# Sheet3.net
KiCad netlist of a schematic drawn in Altium Designer
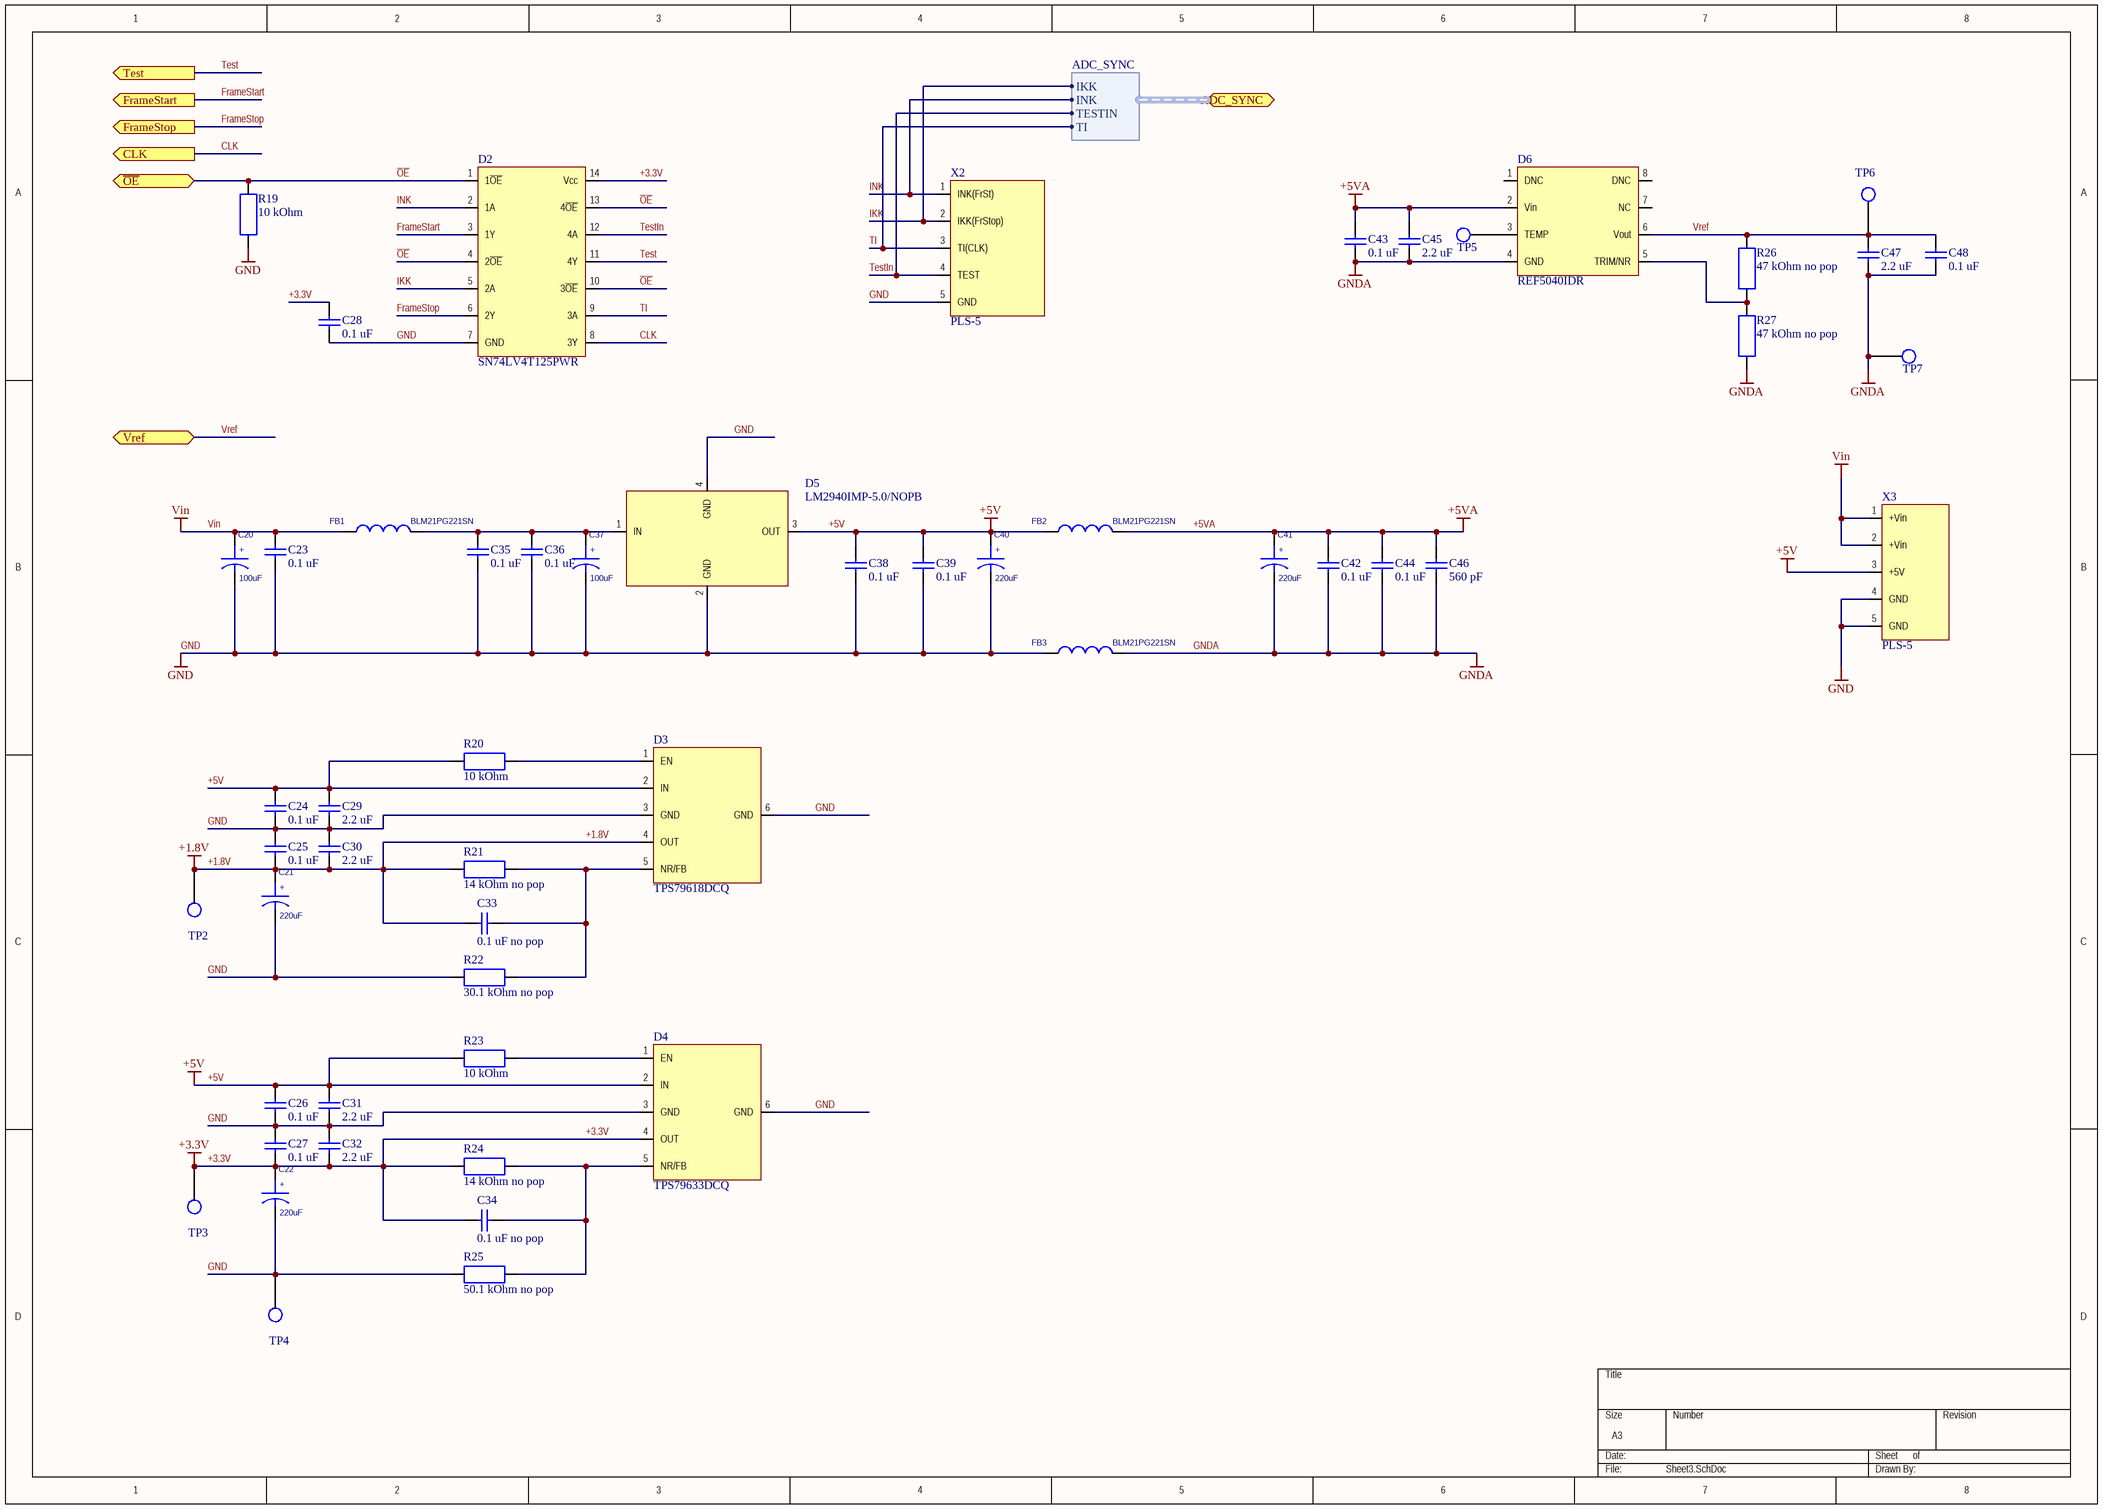
[diagram p0: Sheet3.SchDoc]

(export (version "E")
  (design (tool "Eeschema 10.0.6"))
  (components
    (comp (ref "C20")
      (value "100uF")
      (footprint "TC7343-2917")
      (fields
        (field (name "VENDOR PART#") "495-2256-1-ND")
        (field (name "MFG PART#") "B45196H3107M409")
        (field (name "MFG") "Kemet")
      )
      (libsource (lib "ADClib") (part "CAP TANTAL CASE E"))
    )
    (comp (ref "C21")
      (value "220uF")
      (footprint "TC7343-2917")
      (fields
        (field (name "VENDOR PART#") "495-2256-1-ND")
        (field (name "MFG PART#") "B45196H3107M409")
        (field (name "MFG") "Kemet")
      )
      (libsource (lib "ADClib") (part "CAP TANTAL CASE E"))
    )
    (comp (ref "C22")
      (value "220uF")
      (footprint "TC7343-2917")
      (fields
        (field (name "VENDOR PART#") "495-2256-1-ND")
        (field (name "MFG PART#") "B45196H3107M409")
        (field (name "MFG") "Kemet")
      )
      (libsource (lib "ADClib") (part "CAP TANTAL CASE E"))
    )
    (comp (ref "C23")
      (value "0.1 uF")
      (footprint "CAPC1608N")
      (description "±10%, X7R, 0603")
      (fields (field (name "PUBLISHER") "DS"))
      (libsource (lib "ADClib") (part "CC0603"))
    )
    (comp (ref "C24")
      (value "0.1 uF")
      (footprint "CAPC1608N")
      (description "±10%, X7R, 0603")
      (fields (field (name "PUBLISHER") "DS"))
      (libsource (lib "ADClib") (part "CC0603"))
    )
    (comp (ref "C25")
      (value "0.1 uF")
      (footprint "CAPC1608N")
      (description "±10%, X7R, 0603")
      (fields (field (name "PUBLISHER") "DS"))
      (libsource (lib "ADClib") (part "CC0603"))
    )
    (comp (ref "C26")
      (value "0.1 uF")
      (footprint "CAPC1608N")
      (description "±10%, X7R, 0603")
      (fields (field (name "PUBLISHER") "DS"))
      (libsource (lib "ADClib") (part "CC0603"))
    )
    (comp (ref "C27")
      (value "0.1 uF")
      (footprint "CAPC1608N")
      (description "±10%, X7R, 0603")
      (fields (field (name "PUBLISHER") "DS"))
      (libsource (lib "ADClib") (part "CC0603"))
    )
    (comp (ref "C28")
      (value "0.1 uF")
      (footprint "CAPC1608N")
      (description "±10%, X7R, 0603")
      (fields (field (name "PUBLISHER") "DS"))
      (libsource (lib "ADClib") (part "CC0603"))
    )
    (comp (ref "C29")
      (value "2.2 uF")
      (footprint "CAPC1608N")
      (description "±10%, X7R, 0603")
      (fields (field (name "PUBLISHER") "DS"))
      (libsource (lib "ADClib") (part "CC0603"))
    )
    (comp (ref "C30")
      (value "2.2 uF")
      (footprint "CAPC1608N")
      (description "±10%, X7R, 0603")
      (fields (field (name "PUBLISHER") "DS"))
      (libsource (lib "ADClib") (part "CC0603"))
    )
    (comp (ref "C31")
      (value "2.2 uF")
      (footprint "CAPC1608N")
      (description "±10%, X7R, 0603")
      (fields (field (name "PUBLISHER") "DS"))
      (libsource (lib "ADClib") (part "CC0603"))
    )
    (comp (ref "C32")
      (value "2.2 uF")
      (footprint "CAPC1608N")
      (description "±10%, X7R, 0603")
      (fields (field (name "PUBLISHER") "DS"))
      (libsource (lib "ADClib") (part "CC0603"))
    )
    (comp (ref "C33")
      (value "0.1 uF no pop")
      (footprint "CAPC1608N")
      (description "±10%, X7R, 0603")
      (fields (field (name "PUBLISHER") "DS"))
      (libsource (lib "ADClib") (part "CC0603"))
    )
    (comp (ref "C34")
      (value "0.1 uF no pop")
      (footprint "CAPC1608N")
      (description "±10%, X7R, 0603")
      (fields (field (name "PUBLISHER") "DS"))
      (libsource (lib "ADClib") (part "CC0603"))
    )
    (comp (ref "C35")
      (value "0.1 uF")
      (footprint "CAPC1608N")
      (description "±10%, X7R, 0603")
      (fields (field (name "PUBLISHER") "DS"))
      (libsource (lib "ADClib") (part "CC0603"))
    )
    (comp (ref "C36")
      (value "0.1 uF")
      (footprint "CAPC1608N")
      (description "±10%, X7R, 0603")
      (fields (field (name "PUBLISHER") "DS"))
      (libsource (lib "ADClib") (part "CC0603"))
    )
    (comp (ref "C37")
      (value "100uF")
      (footprint "TC7343-2917")
      (fields
        (field (name "VENDOR PART#") "495-2256-1-ND")
        (field (name "MFG PART#") "B45196H3107M409")
        (field (name "MFG") "Kemet")
      )
      (libsource (lib "ADClib") (part "CAP TANTAL CASE E"))
    )
    (comp (ref "C38")
      (value "0.1 uF")
      (footprint "CAPC1608N")
      (description "±10%, X7R, 0603")
      (fields (field (name "PUBLISHER") "DS"))
      (libsource (lib "ADClib") (part "CC0603"))
    )
    (comp (ref "C39")
      (value "0.1 uF")
      (footprint "CAPC1608N")
      (description "±10%, X7R, 0603")
      (fields (field (name "PUBLISHER") "DS"))
      (libsource (lib "ADClib") (part "CC0603"))
    )
    (comp (ref "C40")
      (value "220uF")
      (footprint "TC7343-2917")
      (fields
        (field (name "VENDOR PART#") "495-2256-1-ND")
        (field (name "MFG PART#") "B45196H3107M409")
        (field (name "MFG") "Kemet")
      )
      (libsource (lib "ADClib") (part "CAP TANTAL CASE E"))
    )
    (comp (ref "C41")
      (value "220uF")
      (footprint "TC7343-2917")
      (fields
        (field (name "VENDOR PART#") "495-2256-1-ND")
        (field (name "MFG PART#") "B45196H3107M409")
        (field (name "MFG") "Kemet")
      )
      (libsource (lib "ADClib") (part "CAP TANTAL CASE E"))
    )
    (comp (ref "C42")
      (value "0.1 uF")
      (footprint "CAPC1608N")
      (description "±10%, X7R, 0603")
      (fields (field (name "PUBLISHER") "DS"))
      (libsource (lib "ADClib") (part "CC0603"))
    )
    (comp (ref "C43")
      (value "0.1 uF")
      (footprint "CAPC1608N")
      (description "±10%, X7R, 0603")
      (fields (field (name "PUBLISHER") "DS"))
      (libsource (lib "ADClib") (part "CC0603"))
    )
    (comp (ref "C44")
      (value "0.1 uF")
      (footprint "CAPC1608N")
      (description "±10%, X7R, 0603")
      (fields (field (name "PUBLISHER") "DS"))
      (libsource (lib "ADClib") (part "CC0603"))
    )
    (comp (ref "C45")
      (value "2.2 uF")
      (footprint "CAPC1608N")
      (description "±10%, X7R, 0603")
      (fields (field (name "PUBLISHER") "DS"))
      (libsource (lib "ADClib") (part "CC0603"))
    )
    (comp (ref "C46")
      (value "560 pF")
      (footprint "CAPC1608N")
      (description "±10%, X7R, 0603")
      (fields (field (name "PUBLISHER") "DS"))
      (libsource (lib "ADClib") (part "CC0603"))
    )
    (comp (ref "C47")
      (value "2.2 uF")
      (footprint "CAPC1608N")
      (description "±10%, X7R, 0603")
      (fields (field (name "PUBLISHER") "DS"))
      (libsource (lib "ADClib") (part "CC0603"))
    )
    (comp (ref "C48")
      (value "0.1 uF")
      (footprint "CAPC1608N")
      (description "±10%, X7R, 0603")
      (fields (field (name "PUBLISHER") "DS"))
      (libsource (lib "ADClib") (part "CC0603"))
    )
    (comp (ref "D2")
      (value "SN74LV4T125PWR")
      (footprint "TSOP65P640X120-14N")
      (description "SN74LV4T125PWR voltage level converter")
      (libsource (lib "ADClib") (part "SN74LV4T125PWR"))
    )
    (comp (ref "D3")
      (value "TPS79618DCQ")
      (footprint "SOT127P706X180-6N")
      (libsource (lib "ADClib") (part "TPS79618DCQ"))
    )
    (comp (ref "D4")
      (value "TPS79633DCQ")
      (footprint "SOT127P706X180-6N")
      (libsource (lib "ADClib") (part "TPS79633DCQ"))
    )
    (comp (ref "D5")
      (value "LM2940IMP-5.0/NOPB")
      (footprint "SOT230P700X180-4N")
      (description "5V LDO")
      (libsource (lib "ADClib") (part "LM2940IMP-5.0/NOPB"))
    )
    (comp (ref "D6") (value "REF5040IDR") (footprint "SO8") (libsource (lib "ADClib") (part "REF5040IDR")))
    (comp (ref "FB1")
      (value "BLM21PG221SN")
      (footprint "INDC2009M")
      (fields
        (field (name "MFG") "Murata")
        (field (name "MFG PART#") "BLM18PG121SN1D")
        (field (name "VENDOR PART#") "490-1037-1-ND")
      )
      (libsource (lib "ADClib") (part "BLM21"))
    )
    (comp (ref "FB2")
      (value "BLM21PG221SN")
      (footprint "INDC2009M")
      (fields
        (field (name "MFG") "Murata")
        (field (name "MFG PART#") "BLM18PG121SN1D")
        (field (name "VENDOR PART#") "490-1037-1-ND")
      )
      (libsource (lib "ADClib") (part "BLM21"))
    )
    (comp (ref "FB3")
      (value "BLM21PG221SN")
      (footprint "INDC2009M")
      (fields
        (field (name "MFG") "Murata")
        (field (name "MFG PART#") "BLM18PG121SN1D")
        (field (name "VENDOR PART#") "490-1037-1-ND")
      )
      (libsource (lib "ADClib") (part "BLM21"))
    )
    (comp (ref "R19")
      (value "10 kOhm")
      (footprint "RESC1608N")
      (description "±5%, 0603")
      (fields (field (name "PUBLISHER") "DS"))
      (libsource (lib "ADClib") (part "RES0603"))
    )
    (comp (ref "R20")
      (value "10 kOhm")
      (footprint "RESC1608N")
      (description "±5%, 0603")
      (fields (field (name "PUBLISHER") "DS"))
      (libsource (lib "ADClib") (part "RES0603"))
    )
    (comp (ref "R21")
      (value "14 kOhm no pop")
      (footprint "RESC1608N")
      (description "±5%, 0603")
      (fields (field (name "PUBLISHER") "DS"))
      (libsource (lib "ADClib") (part "RES0603"))
    )
    (comp (ref "R22")
      (value "30.1 kOhm no pop")
      (footprint "RESC1608N")
      (description "±5%, 0603")
      (fields (field (name "PUBLISHER") "DS"))
      (libsource (lib "ADClib") (part "RES0603"))
    )
    (comp (ref "R23")
      (value "10 kOhm")
      (footprint "RESC1608N")
      (description "±5%, 0603")
      (fields (field (name "PUBLISHER") "DS"))
      (libsource (lib "ADClib") (part "RES0603"))
    )
    (comp (ref "R24")
      (value "14 kOhm no pop")
      (footprint "RESC1608N")
      (description "±5%, 0603")
      (fields (field (name "PUBLISHER") "DS"))
      (libsource (lib "ADClib") (part "RES0603"))
    )
    (comp (ref "R25")
      (value "50.1 kOhm no pop")
      (footprint "RESC1608N")
      (description "±5%, 0603")
      (fields (field (name "PUBLISHER") "DS"))
      (libsource (lib "ADClib") (part "RES0603"))
    )
    (comp (ref "R26")
      (value "47 kOhm no pop")
      (footprint "RESC1608N")
      (description "±5%, 0603")
      (fields (field (name "PUBLISHER") "DS"))
      (libsource (lib "ADClib") (part "RES0603"))
    )
    (comp (ref "R27")
      (value "47 kOhm no pop")
      (footprint "RESC1608N")
      (description "±5%, 0603")
      (fields (field (name "PUBLISHER") "DS"))
      (libsource (lib "ADClib") (part "RES0603"))
    )
    (comp (ref "TP2") (value "PLS-1") (footprint "TPSW") (libsource (lib "ADClib") (part "PLS-1")))
    (comp (ref "TP3") (value "PLS-1") (footprint "TPSW") (libsource (lib "ADClib") (part "PLS-1")))
    (comp (ref "TP4") (value "PLS-1") (footprint "TPSW") (libsource (lib "ADClib") (part "PLS-1")))
    (comp (ref "TP5") (value "PLS-1") (footprint "TPSW") (libsource (lib "ADClib") (part "PLS-1")))
    (comp (ref "TP6") (value "PLS-1") (footprint "TPSW") (libsource (lib "ADClib") (part "PLS-1")))
    (comp (ref "TP7") (value "PLS-1") (footprint "TPSW") (libsource (lib "ADClib") (part "PLS-1")))
    (comp (ref "X2") (value "PLS-5") (footprint "PLS-5") (libsource (lib "ADClib") (part "SYNCIN")))
    (comp (ref "X3") (value "PLS-5") (footprint "PLS-5") (libsource (lib "ADClib") (part "PWRIN")))
  )
  (nets
    (net (code "2") (name "+1.8V") (class "Default")
      (node (ref "C21") (pin "1") (pinfunction "Positive_1") (pintype "passive"))
      (node (ref "C25") (pin "1") (pinfunction "1_1") (pintype "passive"))
      (node (ref "C30") (pin "1") (pinfunction "1_1") (pintype "passive"))
      (node (ref "C33") (pin "2") (pinfunction "2_2") (pintype "passive"))
      (node (ref "D3") (pin "4") (pinfunction "OUT_4") (pintype "passive"))
      (node (ref "R21") (pin "2") (pinfunction "2_2") (pintype "passive"))
      (node (ref "TP2") (pin "1") (pinfunction "1_1") (pintype "passive"))
    )
    (net (code "3") (name "+3.3V") (class "Default")
      (node (ref "C22") (pin "1") (pinfunction "Positive_1") (pintype "passive"))
      (node (ref "C27") (pin "1") (pinfunction "1_1") (pintype "passive"))
      (node (ref "C28") (pin "2") (pinfunction "2_2") (pintype "passive"))
      (node (ref "C32") (pin "1") (pinfunction "1_1") (pintype "passive"))
      (node (ref "C34") (pin "2") (pinfunction "2_2") (pintype "passive"))
      (node (ref "D2") (pin "14") (pinfunction "Vcc_14") (pintype "passive"))
      (node (ref "D4") (pin "4") (pinfunction "OUT_4") (pintype "passive"))
      (node (ref "R24") (pin "2") (pinfunction "2_2") (pintype "passive"))
      (node (ref "TP3") (pin "1") (pinfunction "1_1") (pintype "passive"))
    )
    (net (code "4") (name "+5V") (class "Default")
      (node (ref "C24") (pin "2") (pinfunction "2_2") (pintype "passive"))
      (node (ref "C26") (pin "2") (pinfunction "2_2") (pintype "passive"))
      (node (ref "C29") (pin "2") (pinfunction "2_2") (pintype "passive"))
      (node (ref "C31") (pin "2") (pinfunction "2_2") (pintype "passive"))
      (node (ref "C38") (pin "2") (pinfunction "2_2") (pintype "passive"))
      (node (ref "C39") (pin "2") (pinfunction "2_2") (pintype "passive"))
      (node (ref "C40") (pin "1") (pinfunction "Positive_1") (pintype "passive"))
      (node (ref "D3") (pin "2") (pinfunction "IN_2") (pintype "passive"))
      (node (ref "D4") (pin "2") (pinfunction "IN_2") (pintype "passive"))
      (node (ref "D5") (pin "3") (pinfunction "OUT_3") (pintype "passive"))
      (node (ref "FB2") (pin "1") (pinfunction "1_1") (pintype "passive"))
      (node (ref "R20") (pin "2") (pinfunction "2_2") (pintype "passive"))
      (node (ref "R23") (pin "2") (pinfunction "2_2") (pintype "passive"))
      (node (ref "X3") (pin "3") (pinfunction "+5V_3") (pintype "passive"))
    )
    (net (code "5") (name "+5VA") (class "Default")
      (node (ref "C41") (pin "1") (pinfunction "Positive_1") (pintype "passive"))
      (node (ref "C42") (pin "2") (pinfunction "2_2") (pintype "passive"))
      (node (ref "C43") (pin "2") (pinfunction "2_2") (pintype "passive"))
      (node (ref "C44") (pin "2") (pinfunction "2_2") (pintype "passive"))
      (node (ref "C45") (pin "2") (pinfunction "2_2") (pintype "passive"))
      (node (ref "C46") (pin "2") (pinfunction "2_2") (pintype "passive"))
      (node (ref "D6") (pin "2") (pinfunction "Vin_2") (pintype "passive"))
      (node (ref "FB2") (pin "2") (pinfunction "2_2") (pintype "passive"))
    )
    (net (code "6") (name "/CLK") (class "Default")
      (node (ref "D2") (pin "8") (pinfunction "3Y_8") (pintype "passive"))
    )
    (net (code "7") (name "/FrameStart") (class "Default")
      (node (ref "D2") (pin "3") (pinfunction "1Y_3") (pintype "passive"))
    )
    (net (code "8") (name "/FrameStop") (class "Default")
      (node (ref "D2") (pin "6") (pinfunction "2Y_6") (pintype "passive"))
    )
    (net (code "9") (name "/IKK") (class "Default")
      (node (ref "D2") (pin "5") (pinfunction "2A_5") (pintype "passive"))
      (node (ref "X2") (pin "2") (pinfunction "IKK(FrStop)_2") (pintype "passive"))
    )
    (net (code "10") (name "/INK") (class "Default")
      (node (ref "D2") (pin "2") (pinfunction "1A_2") (pintype "passive"))
      (node (ref "X2") (pin "1") (pinfunction "INK(FrSt)_1") (pintype "passive"))
    )
    (net (code "11") (name "/TI") (class "Default")
      (node (ref "D2") (pin "9") (pinfunction "3A_9") (pintype "passive"))
      (node (ref "X2") (pin "3") (pinfunction "TI(CLK)_3") (pintype "passive"))
    )
    (net (code "12") (name "/Test") (class "Default")
      (node (ref "D2") (pin "11") (pinfunction "4Y_11") (pintype "passive"))
    )
    (net (code "13") (name "/TestIn") (class "Default")
      (node (ref "D2") (pin "12") (pinfunction "4A_12") (pintype "passive"))
      (node (ref "X2") (pin "4") (pinfunction "TEST_4") (pintype "passive"))
    )
    (net (code "14") (name "/Vref") (class "Default")
      (node (ref "C47") (pin "2") (pinfunction "2_2") (pintype "passive"))
      (node (ref "C48") (pin "2") (pinfunction "2_2") (pintype "passive"))
      (node (ref "D6") (pin "6") (pinfunction "Vout_6") (pintype "passive"))
      (node (ref "R26") (pin "2") (pinfunction "2_2") (pintype "passive"))
      (node (ref "TP6") (pin "1") (pinfunction "1_1") (pintype "passive"))
    )
    (net (code "16") (name "/~{OE}") (class "Default")
      (node (ref "D2") (pin "1") (pinfunction "1~{OE}_1") (pintype "passive"))
      (node (ref "D2") (pin "10") (pinfunction "3~{OE}_10") (pintype "passive"))
      (node (ref "D2") (pin "13") (pinfunction "4~{OE}_13") (pintype "passive"))
      (node (ref "D2") (pin "4") (pinfunction "2~{OE}_4") (pintype "passive"))
      (node (ref "R19") (pin "2") (pinfunction "2_2") (pintype "passive"))
    )
    (net (code "17") (name "GND") (class "Default")
      (node (ref "C20") (pin "2") (pinfunction "Negative_2") (pintype "passive"))
      (node (ref "C21") (pin "2") (pinfunction "Negative_2") (pintype "passive"))
      (node (ref "C22") (pin "2") (pinfunction "Negative_2") (pintype "passive"))
      (node (ref "C23") (pin "1") (pinfunction "1_1") (pintype "passive"))
      (node (ref "C24") (pin "1") (pinfunction "1_1") (pintype "passive"))
      (node (ref "C25") (pin "2") (pinfunction "2_2") (pintype "passive"))
      (node (ref "C26") (pin "1") (pinfunction "1_1") (pintype "passive"))
      (node (ref "C27") (pin "2") (pinfunction "2_2") (pintype "passive"))
      (node (ref "C28") (pin "1") (pinfunction "1_1") (pintype "passive"))
      (node (ref "C29") (pin "1") (pinfunction "1_1") (pintype "passive"))
      (node (ref "C30") (pin "2") (pinfunction "2_2") (pintype "passive"))
      (node (ref "C31") (pin "1") (pinfunction "1_1") (pintype "passive"))
      (node (ref "C32") (pin "2") (pinfunction "2_2") (pintype "passive"))
      (node (ref "C35") (pin "1") (pinfunction "1_1") (pintype "passive"))
      (node (ref "C36") (pin "1") (pinfunction "1_1") (pintype "passive"))
      (node (ref "C37") (pin "2") (pinfunction "Negative_2") (pintype "passive"))
      (node (ref "C38") (pin "1") (pinfunction "1_1") (pintype "passive"))
      (node (ref "C39") (pin "1") (pinfunction "1_1") (pintype "passive"))
      (node (ref "C40") (pin "2") (pinfunction "Negative_2") (pintype "passive"))
      (node (ref "D2") (pin "7") (pinfunction "GND_7") (pintype "passive"))
      (node (ref "D3") (pin "3") (pinfunction "GND_3") (pintype "passive"))
      (node (ref "D3") (pin "6") (pinfunction "GND_6") (pintype "passive"))
      (node (ref "D4") (pin "3") (pinfunction "GND_3") (pintype "passive"))
      (node (ref "D4") (pin "6") (pinfunction "GND_6") (pintype "passive"))
      (node (ref "D5") (pin "2") (pinfunction "GND_2") (pintype "passive"))
      (node (ref "D5") (pin "4") (pinfunction "GND_4") (pintype "passive"))
      (node (ref "FB3") (pin "1") (pinfunction "1_1") (pintype "passive"))
      (node (ref "R19") (pin "1") (pinfunction "1_1") (pintype "passive"))
      (node (ref "R22") (pin "2") (pinfunction "2_2") (pintype "passive"))
      (node (ref "R25") (pin "2") (pinfunction "2_2") (pintype "passive"))
      (node (ref "TP4") (pin "1") (pinfunction "1_1") (pintype "passive"))
      (node (ref "X2") (pin "5") (pinfunction "GND_5") (pintype "passive"))
      (node (ref "X3") (pin "4") (pinfunction "GND_4") (pintype "passive"))
      (node (ref "X3") (pin "5") (pinfunction "GND_5") (pintype "passive"))
    )
    (net (code "18") (name "GNDA") (class "Default")
      (node (ref "C41") (pin "2") (pinfunction "Negative_2") (pintype "passive"))
      (node (ref "C42") (pin "1") (pinfunction "1_1") (pintype "passive"))
      (node (ref "C43") (pin "1") (pinfunction "1_1") (pintype "passive"))
      (node (ref "C44") (pin "1") (pinfunction "1_1") (pintype "passive"))
      (node (ref "C45") (pin "1") (pinfunction "1_1") (pintype "passive"))
      (node (ref "C46") (pin "1") (pinfunction "1_1") (pintype "passive"))
      (node (ref "C47") (pin "1") (pinfunction "1_1") (pintype "passive"))
      (node (ref "C48") (pin "1") (pinfunction "1_1") (pintype "passive"))
      (node (ref "D6") (pin "4") (pinfunction "GND_4") (pintype "passive"))
      (node (ref "FB3") (pin "2") (pinfunction "2_2") (pintype "passive"))
      (node (ref "R27") (pin "2") (pinfunction "2_2") (pintype "passive"))
      (node (ref "TP7") (pin "1") (pinfunction "1_1") (pintype "passive"))
    )
    (net (code "19") (name "Net-(C37-Positive)") (class "Default")
      (node (ref "C35") (pin "2") (pinfunction "2_2") (pintype "passive"))
      (node (ref "C36") (pin "2") (pinfunction "2_2") (pintype "passive"))
      (node (ref "C37") (pin "1") (pinfunction "Positive_1") (pintype "passive"))
      (node (ref "D5") (pin "1") (pinfunction "IN_1") (pintype "passive"))
      (node (ref "FB1") (pin "2") (pinfunction "2_2") (pintype "passive"))
    )
    (net (code "20") (name "Net-(D3-EN)") (class "Default")
      (node (ref "D3") (pin "1") (pinfunction "EN_1") (pintype "passive"))
      (node (ref "R20") (pin "1") (pinfunction "1_1") (pintype "passive"))
    )
    (net (code "21") (name "Net-(D3-NR{slash}FB)") (class "Default")
      (node (ref "C33") (pin "1") (pinfunction "1_1") (pintype "passive"))
      (node (ref "D3") (pin "5") (pinfunction "NR/FB_5") (pintype "passive"))
      (node (ref "R21") (pin "1") (pinfunction "1_1") (pintype "passive"))
      (node (ref "R22") (pin "1") (pinfunction "1_1") (pintype "passive"))
    )
    (net (code "22") (name "Net-(D4-EN)") (class "Default")
      (node (ref "D4") (pin "1") (pinfunction "EN_1") (pintype "passive"))
      (node (ref "R23") (pin "1") (pinfunction "1_1") (pintype "passive"))
    )
    (net (code "23") (name "Net-(D4-NR{slash}FB)") (class "Default")
      (node (ref "C34") (pin "1") (pinfunction "1_1") (pintype "passive"))
      (node (ref "D4") (pin "5") (pinfunction "NR/FB_5") (pintype "passive"))
      (node (ref "R24") (pin "1") (pinfunction "1_1") (pintype "passive"))
      (node (ref "R25") (pin "1") (pinfunction "1_1") (pintype "passive"))
    )
    (net (code "24") (name "Net-(D6-TEMP)") (class "Default")
      (node (ref "D6") (pin "3") (pinfunction "TEMP_3") (pintype "passive"))
      (node (ref "TP5") (pin "1") (pinfunction "1_1") (pintype "passive"))
    )
    (net (code "25") (name "Net-(D6-TRIM{slash}NR)") (class "Default")
      (node (ref "D6") (pin "5") (pinfunction "TRIM/NR_5") (pintype "passive"))
      (node (ref "R26") (pin "1") (pinfunction "1_1") (pintype "passive"))
      (node (ref "R27") (pin "1") (pinfunction "1_1") (pintype "passive"))
    )
    (net (code "26") (name "Vin") (class "Default")
      (node (ref "C20") (pin "1") (pinfunction "Positive_1") (pintype "passive"))
      (node (ref "C23") (pin "2") (pinfunction "2_2") (pintype "passive"))
      (node (ref "FB1") (pin "1") (pinfunction "1_1") (pintype "passive"))
      (node (ref "X3") (pin "1") (pinfunction "+Vin_1") (pintype "passive"))
      (node (ref "X3") (pin "2") (pinfunction "+Vin_2") (pintype "passive"))
    )
    (net (code "27") (name "unconnected-(D6-DNC-Pad1)") (class "Default")
      (node (ref "D6") (pin "1") (pinfunction "DNC_1") (pintype "passive"))
    )
    (net (code "28") (name "unconnected-(D6-DNC-Pad8)") (class "Default")
      (node (ref "D6") (pin "8") (pinfunction "DNC_8") (pintype "passive"))
    )
    (net (code "29") (name "unconnected-(D6-NC-Pad7)") (class "Default")
      (node (ref "D6") (pin "7") (pinfunction "NC_7") (pintype "passive"))
    )
  )
)
